# proto4-duplex.net
KiCad netlist of a schematic drawn in EAGLE
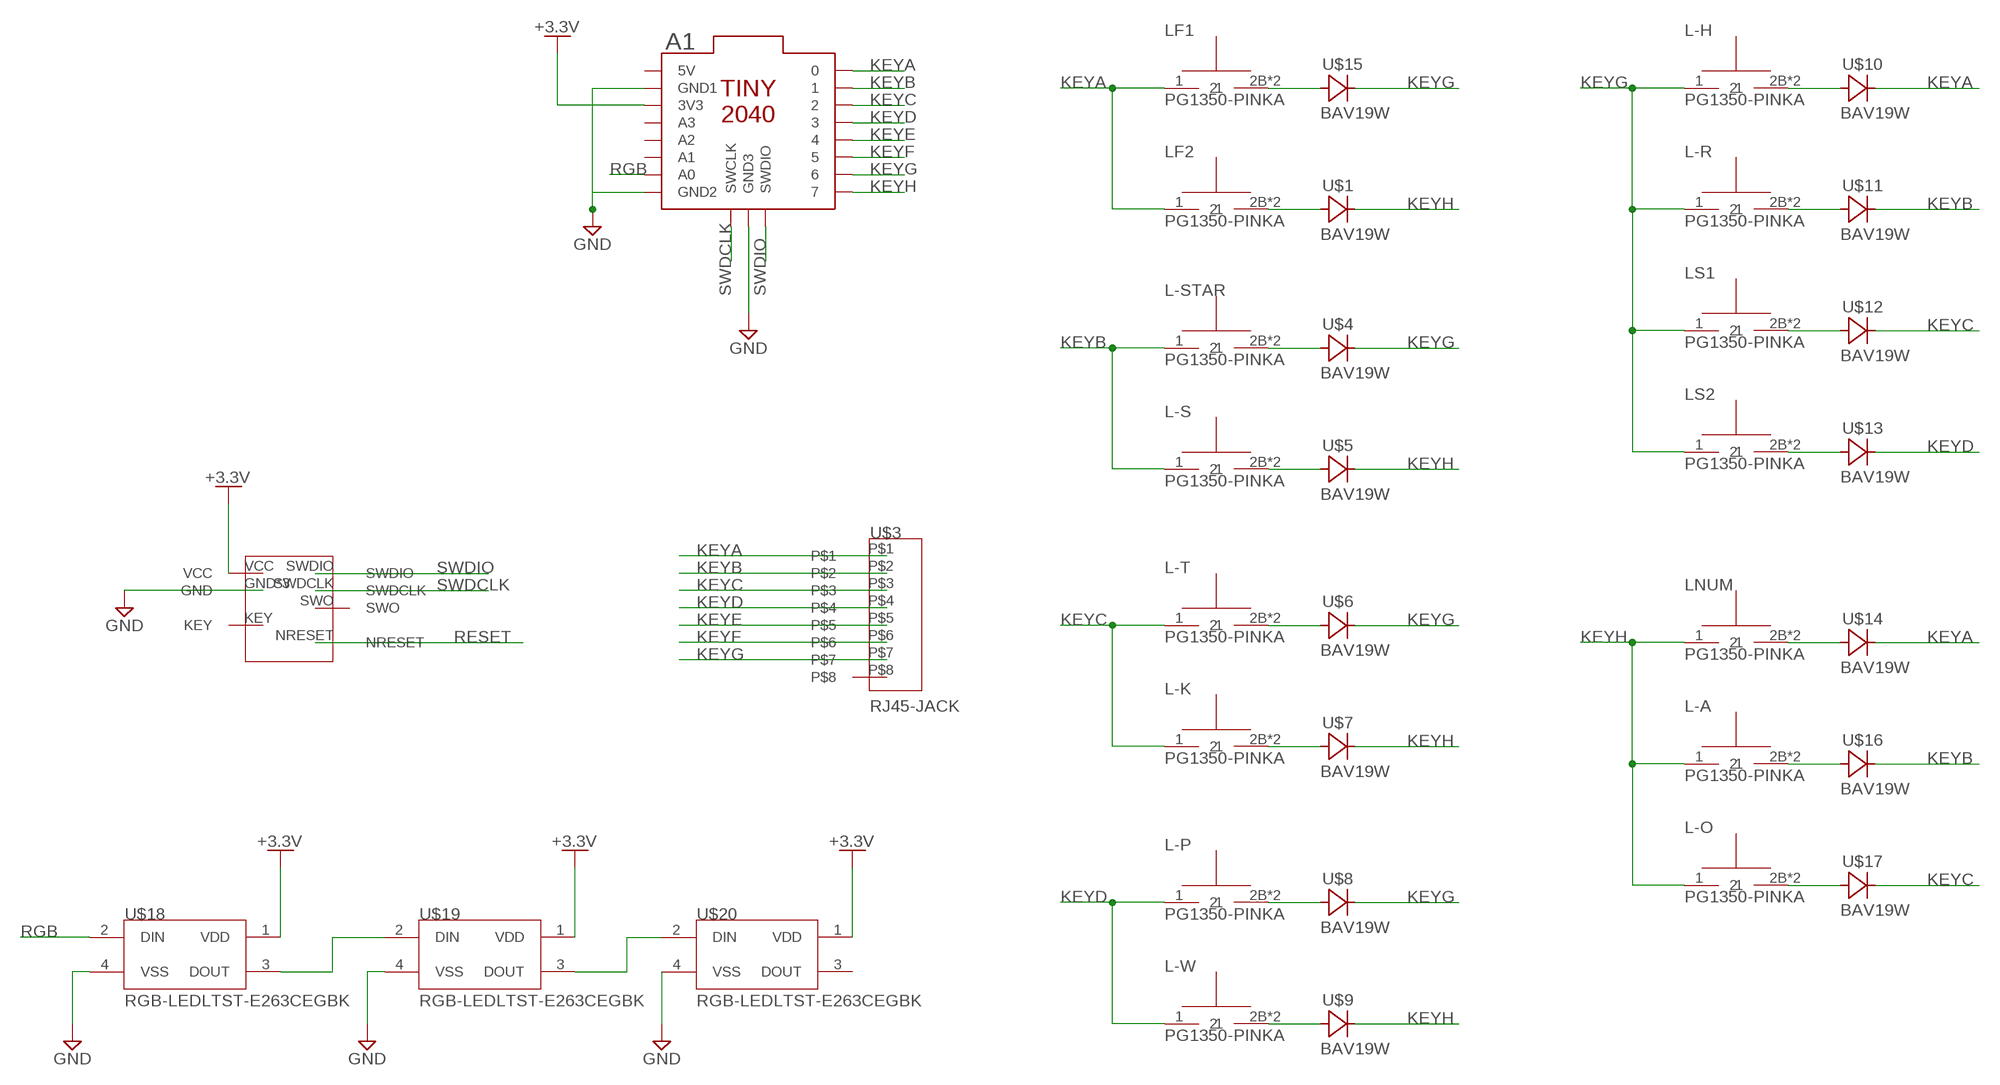
[diagram p0: schematic, sheet 1]

(export (version "E")
  (design (tool "Eeschema 10.0.6"))
  (components
    (comp (ref "A1")
      (value "TINY2040")
      (footprint "eagle-import:TINY2040")
      (libsource (lib "eagle-import") (part "TINY2040"))
    )
    (comp (ref "L-A")
      (value "PG1350-PINKA")
      (footprint "eagle-import:PG1350")
      (libsource (lib "eagle-import") (part "PG1350-PINKA"))
    )
    (comp (ref "L-H")
      (value "PG1350-PINKA")
      (footprint "eagle-import:PG1350")
      (libsource (lib "eagle-import") (part "PG1350-PINKA"))
    )
    (comp (ref "L-K")
      (value "PG1350-PINKA")
      (footprint "eagle-import:PG1350")
      (libsource (lib "eagle-import") (part "PG1350-PINKA"))
    )
    (comp (ref "L-O")
      (value "PG1350-PINKA")
      (footprint "eagle-import:PG1350")
      (libsource (lib "eagle-import") (part "PG1350-PINKA"))
    )
    (comp (ref "L-P")
      (value "PG1350-PINKA")
      (footprint "eagle-import:PG1350")
      (libsource (lib "eagle-import") (part "PG1350-PINKA"))
    )
    (comp (ref "L-R")
      (value "PG1350-PINKA")
      (footprint "eagle-import:PG1350")
      (libsource (lib "eagle-import") (part "PG1350-PINKA"))
    )
    (comp (ref "L-S")
      (value "PG1350-PINKA")
      (footprint "eagle-import:PG1350")
      (libsource (lib "eagle-import") (part "PG1350-PINKA"))
    )
    (comp (ref "L-STAR")
      (value "PG1350-PINKA")
      (footprint "eagle-import:PG1350")
      (libsource (lib "eagle-import") (part "PG1350-PINKA"))
    )
    (comp (ref "L-T")
      (value "PG1350-PINKA")
      (footprint "eagle-import:PG1350")
      (libsource (lib "eagle-import") (part "PG1350-PINKA"))
    )
    (comp (ref "L-W")
      (value "PG1350-PINKA")
      (footprint "eagle-import:PG1350")
      (libsource (lib "eagle-import") (part "PG1350-PINKA"))
    )
    (comp (ref "LF1")
      (value "PG1350-PINKA")
      (footprint "eagle-import:PG1350")
      (libsource (lib "eagle-import") (part "PG1350-PINKA"))
    )
    (comp (ref "LF2")
      (value "PG1350-PINKA")
      (footprint "eagle-import:PG1350")
      (libsource (lib "eagle-import") (part "PG1350-PINKA"))
    )
    (comp (ref "LNUM")
      (value "PG1350-PINKA")
      (footprint "eagle-import:PG1350")
      (libsource (lib "eagle-import") (part "PG1350-PINKA"))
    )
    (comp (ref "LS1")
      (value "PG1350-PINKA")
      (footprint "eagle-import:PG1350")
      (libsource (lib "eagle-import") (part "PG1350-PINKA"))
    )
    (comp (ref "LS2")
      (value "PG1350-PINKA")
      (footprint "eagle-import:PG1350")
      (libsource (lib "eagle-import") (part "PG1350-PINKA"))
    )
    (comp (ref "U$1")
      (value "BAV19W")
      (footprint "eagle-import:SOD123")
      (libsource (lib "eagle-import") (part "BAV19W"))
    )
    (comp (ref "U$2")
      (value "CORTEX-M0")
      (footprint "eagle-import:CORTEX-M10")
      (libsource (lib "eagle-import") (part "CORTEX-M0"))
    )
    (comp (ref "U$3")
      (value "RJ45-JACK")
      (footprint "eagle-import:C-BMJ-0051-RJ45")
      (libsource (lib "eagle-import") (part "RJ45-JACK"))
    )
    (comp (ref "U$4")
      (value "BAV19W")
      (footprint "eagle-import:SOD123")
      (libsource (lib "eagle-import") (part "BAV19W"))
    )
    (comp (ref "U$5")
      (value "BAV19W")
      (footprint "eagle-import:SOD123")
      (libsource (lib "eagle-import") (part "BAV19W"))
    )
    (comp (ref "U$6")
      (value "BAV19W")
      (footprint "eagle-import:SOD123")
      (libsource (lib "eagle-import") (part "BAV19W"))
    )
    (comp (ref "U$7")
      (value "BAV19W")
      (footprint "eagle-import:SOD123")
      (libsource (lib "eagle-import") (part "BAV19W"))
    )
    (comp (ref "U$8")
      (value "BAV19W")
      (footprint "eagle-import:SOD123")
      (libsource (lib "eagle-import") (part "BAV19W"))
    )
    (comp (ref "U$9")
      (value "BAV19W")
      (footprint "eagle-import:SOD123")
      (libsource (lib "eagle-import") (part "BAV19W"))
    )
    (comp (ref "U$10")
      (value "BAV19W")
      (footprint "eagle-import:SOD123")
      (libsource (lib "eagle-import") (part "BAV19W"))
    )
    (comp (ref "U$11")
      (value "BAV19W")
      (footprint "eagle-import:SOD123")
      (libsource (lib "eagle-import") (part "BAV19W"))
    )
    (comp (ref "U$12")
      (value "BAV19W")
      (footprint "eagle-import:SOD123")
      (libsource (lib "eagle-import") (part "BAV19W"))
    )
    (comp (ref "U$13")
      (value "BAV19W")
      (footprint "eagle-import:SOD123")
      (libsource (lib "eagle-import") (part "BAV19W"))
    )
    (comp (ref "U$14")
      (value "BAV19W")
      (footprint "eagle-import:SOD123")
      (libsource (lib "eagle-import") (part "BAV19W"))
    )
    (comp (ref "U$15")
      (value "BAV19W")
      (footprint "eagle-import:SOD123")
      (libsource (lib "eagle-import") (part "BAV19W"))
    )
    (comp (ref "U$16")
      (value "BAV19W")
      (footprint "eagle-import:SOD123")
      (libsource (lib "eagle-import") (part "BAV19W"))
    )
    (comp (ref "U$17")
      (value "BAV19W")
      (footprint "eagle-import:SOD123")
      (libsource (lib "eagle-import") (part "BAV19W"))
    )
    (comp (ref "U$18")
      (value "RGB-LEDLTST-E263CEGBK")
      (footprint "eagle-import:DFN180X180X65-2")
      (libsource (lib "eagle-import") (part "RGB-LEDLTST-E263CEGBK"))
    )
    (comp (ref "U$19")
      (value "RGB-LEDLTST-E263CEGBK")
      (footprint "eagle-import:DFN180X180X65-2")
      (libsource (lib "eagle-import") (part "RGB-LEDLTST-E263CEGBK"))
    )
    (comp (ref "U$20")
      (value "RGB-LEDLTST-E263CEGBK")
      (footprint "eagle-import:DFN180X180X65-2")
      (libsource (lib "eagle-import") (part "RGB-LEDLTST-E263CEGBK"))
    )
  )
  (nets
    (net (code "1") (name "+3.3V") (class "Default")
      (node (ref "A1") (pin "3V3") (pinfunction "3V3_3V3") (pintype "bidirectional"))
      (node (ref "U$18") (pin "1") (pinfunction "VDD_1") (pintype "power_in"))
      (node (ref "U$19") (pin "1") (pinfunction "VDD_1") (pintype "power_in"))
      (node (ref "U$20") (pin "1") (pinfunction "VDD_1") (pintype "power_in"))
    )
    (net (code "2") (name "/KEYA") (class "Default")
      (node (ref "A1") (pin "0") (pinfunction "0_0") (pintype "bidirectional"))
      (node (ref "LF1") (pin "1") (pinfunction "1_1") (pintype "passive"))
      (node (ref "LF2") (pin "1") (pinfunction "1_1") (pintype "passive"))
      (node (ref "U$10") (pin "C") (pinfunction "C_C") (pintype "passive"))
      (node (ref "U$14") (pin "C") (pinfunction "C_C") (pintype "passive"))
      (node (ref "U$3") (pin "P$1") (pinfunction "P$1_P$1") (pintype "bidirectional"))
    )
    (net (code "3") (name "/KEYB") (class "Default")
      (node (ref "A1") (pin "1") (pinfunction "1_1") (pintype "bidirectional"))
      (node (ref "L-S") (pin "1") (pinfunction "1_1") (pintype "passive"))
      (node (ref "L-STAR") (pin "1") (pinfunction "1_1") (pintype "passive"))
      (node (ref "U$11") (pin "C") (pinfunction "C_C") (pintype "passive"))
      (node (ref "U$16") (pin "C") (pinfunction "C_C") (pintype "passive"))
      (node (ref "U$3") (pin "P$2") (pinfunction "P$2_P$2") (pintype "bidirectional"))
    )
    (net (code "4") (name "/KEYC") (class "Default")
      (node (ref "A1") (pin "2") (pinfunction "2_2") (pintype "bidirectional"))
      (node (ref "L-K") (pin "1") (pinfunction "1_1") (pintype "passive"))
      (node (ref "L-T") (pin "1") (pinfunction "1_1") (pintype "passive"))
      (node (ref "U$12") (pin "C") (pinfunction "C_C") (pintype "passive"))
      (node (ref "U$17") (pin "C") (pinfunction "C_C") (pintype "passive"))
      (node (ref "U$3") (pin "P$3") (pinfunction "P$3_P$3") (pintype "bidirectional"))
    )
    (net (code "5") (name "/KEYD") (class "Default")
      (node (ref "A1") (pin "3") (pinfunction "3_3") (pintype "bidirectional"))
      (node (ref "L-P") (pin "1") (pinfunction "1_1") (pintype "passive"))
      (node (ref "L-W") (pin "1") (pinfunction "1_1") (pintype "passive"))
      (node (ref "U$13") (pin "C") (pinfunction "C_C") (pintype "passive"))
      (node (ref "U$3") (pin "P$4") (pinfunction "P$4_P$4") (pintype "bidirectional"))
    )
    (net (code "6") (name "/KEYE") (class "Default")
      (node (ref "A1") (pin "4") (pinfunction "4_4") (pintype "bidirectional"))
      (node (ref "U$3") (pin "P$5") (pinfunction "P$5_P$5") (pintype "bidirectional"))
    )
    (net (code "7") (name "/KEYF") (class "Default")
      (node (ref "A1") (pin "5") (pinfunction "5_5") (pintype "bidirectional"))
      (node (ref "U$3") (pin "P$6") (pinfunction "P$6_P$6") (pintype "bidirectional"))
    )
    (net (code "8") (name "/KEYG") (class "Default")
      (node (ref "A1") (pin "6") (pinfunction "6_6") (pintype "bidirectional"))
      (node (ref "L-H") (pin "1") (pinfunction "1_1") (pintype "passive"))
      (node (ref "L-R") (pin "1") (pinfunction "1_1") (pintype "passive"))
      (node (ref "LS1") (pin "1") (pinfunction "1_1") (pintype "passive"))
      (node (ref "LS2") (pin "1") (pinfunction "1_1") (pintype "passive"))
      (node (ref "U$15") (pin "C") (pinfunction "C_C") (pintype "passive"))
      (node (ref "U$3") (pin "P$7") (pinfunction "P$7_P$7") (pintype "bidirectional"))
      (node (ref "U$4") (pin "C") (pinfunction "C_C") (pintype "passive"))
      (node (ref "U$6") (pin "C") (pinfunction "C_C") (pintype "passive"))
      (node (ref "U$8") (pin "C") (pinfunction "C_C") (pintype "passive"))
    )
    (net (code "9") (name "/KEYH") (class "Default")
      (node (ref "A1") (pin "7") (pinfunction "7_7") (pintype "bidirectional"))
      (node (ref "L-A") (pin "1") (pinfunction "1_1") (pintype "passive"))
      (node (ref "L-O") (pin "1") (pinfunction "1_1") (pintype "passive"))
      (node (ref "LNUM") (pin "1") (pinfunction "1_1") (pintype "passive"))
      (node (ref "U$1") (pin "C") (pinfunction "C_C") (pintype "passive"))
      (node (ref "U$5") (pin "C") (pinfunction "C_C") (pintype "passive"))
      (node (ref "U$7") (pin "C") (pinfunction "C_C") (pintype "passive"))
      (node (ref "U$9") (pin "C") (pinfunction "C_C") (pintype "passive"))
    )
    (net (code "10") (name "/RESET") (class "Default")
      (node (ref "U$2") (pin "NRESET") (pinfunction "NRESET_NRESET") (pintype "bidirectional"))
    )
    (net (code "11") (name "/RGB") (class "Default")
      (node (ref "A1") (pin "A0") (pinfunction "A0_A0") (pintype "bidirectional"))
      (node (ref "U$18") (pin "2") (pinfunction "DIN_2") (pintype "input"))
    )
    (net (code "12") (name "/SWDCLK") (class "Default")
      (node (ref "A1") (pin "SWCLK") (pinfunction "SWCLK_SWCLK") (pintype "bidirectional"))
      (node (ref "U$2") (pin "SWDCLK") (pinfunction "SWDCLK_SWDCLK") (pintype "bidirectional"))
    )
    (net (code "13") (name "/SWDIO") (class "Default")
      (node (ref "A1") (pin "SWDIO") (pinfunction "SWDIO_SWDIO") (pintype "bidirectional"))
      (node (ref "U$2") (pin "SWDIO") (pinfunction "SWDIO_SWDIO") (pintype "bidirectional"))
    )
    (net (code "14") (name "GND") (class "Default")
      (node (ref "A1") (pin "GND1") (pinfunction "GND1_GND1") (pintype "bidirectional"))
      (node (ref "A1") (pin "GND2") (pinfunction "GND2_GND2") (pintype "bidirectional"))
      (node (ref "A1") (pin "GND3") (pinfunction "GND3_GND3") (pintype "bidirectional"))
      (node (ref "U$18") (pin "4") (pinfunction "VSS_4") (pintype "power_in"))
      (node (ref "U$19") (pin "4") (pinfunction "VSS_4") (pintype "power_in"))
      (node (ref "U$2") (pin "GND") (pinfunction "GND_GND") (pintype "bidirectional"))
      (node (ref "U$2") (pin "GND2") (pinfunction "GND_GND2") (pintype "bidirectional"))
      (node (ref "U$2") (pin "GNDDETEC") (pinfunction "GND_GNDDETEC") (pintype "bidirectional"))
      (node (ref "U$20") (pin "4") (pinfunction "VSS_4") (pintype "power_in"))
    )
    (net (code "15") (name "Net-(L-A-2-Pad2B)") (class "Default")
      (node (ref "L-A") (pin "2B") (pinfunction "2_2B") (pintype "passive"))
      (node (ref "L-A") (pin "2T") (pinfunction "2_2T") (pintype "passive"))
      (node (ref "U$16") (pin "A") (pinfunction "A_A") (pintype "passive"))
    )
    (net (code "16") (name "Net-(L-H-2-Pad2B)") (class "Default")
      (node (ref "L-H") (pin "2B") (pinfunction "2_2B") (pintype "passive"))
      (node (ref "L-H") (pin "2T") (pinfunction "2_2T") (pintype "passive"))
      (node (ref "U$10") (pin "A") (pinfunction "A_A") (pintype "passive"))
    )
    (net (code "17") (name "Net-(L-K-2-Pad2B)") (class "Default")
      (node (ref "L-K") (pin "2B") (pinfunction "2_2B") (pintype "passive"))
      (node (ref "L-K") (pin "2T") (pinfunction "2_2T") (pintype "passive"))
      (node (ref "U$7") (pin "A") (pinfunction "A_A") (pintype "passive"))
    )
    (net (code "18") (name "Net-(L-O-2-Pad2B)") (class "Default")
      (node (ref "L-O") (pin "2B") (pinfunction "2_2B") (pintype "passive"))
      (node (ref "L-O") (pin "2T") (pinfunction "2_2T") (pintype "passive"))
      (node (ref "U$17") (pin "A") (pinfunction "A_A") (pintype "passive"))
    )
    (net (code "19") (name "Net-(L-P-2-Pad2B)") (class "Default")
      (node (ref "L-P") (pin "2B") (pinfunction "2_2B") (pintype "passive"))
      (node (ref "L-P") (pin "2T") (pinfunction "2_2T") (pintype "passive"))
      (node (ref "U$8") (pin "A") (pinfunction "A_A") (pintype "passive"))
    )
    (net (code "20") (name "Net-(L-R-2-Pad2B)") (class "Default")
      (node (ref "L-R") (pin "2B") (pinfunction "2_2B") (pintype "passive"))
      (node (ref "L-R") (pin "2T") (pinfunction "2_2T") (pintype "passive"))
      (node (ref "U$11") (pin "A") (pinfunction "A_A") (pintype "passive"))
    )
    (net (code "21") (name "Net-(L-S-2-Pad2B)") (class "Default")
      (node (ref "L-S") (pin "2B") (pinfunction "2_2B") (pintype "passive"))
      (node (ref "L-S") (pin "2T") (pinfunction "2_2T") (pintype "passive"))
      (node (ref "U$5") (pin "A") (pinfunction "A_A") (pintype "passive"))
    )
    (net (code "22") (name "Net-(L-STAR-2-Pad2B)") (class "Default")
      (node (ref "L-STAR") (pin "2B") (pinfunction "2_2B") (pintype "passive"))
      (node (ref "L-STAR") (pin "2T") (pinfunction "2_2T") (pintype "passive"))
      (node (ref "U$4") (pin "A") (pinfunction "A_A") (pintype "passive"))
    )
    (net (code "23") (name "Net-(L-T-2-Pad2B)") (class "Default")
      (node (ref "L-T") (pin "2B") (pinfunction "2_2B") (pintype "passive"))
      (node (ref "L-T") (pin "2T") (pinfunction "2_2T") (pintype "passive"))
      (node (ref "U$6") (pin "A") (pinfunction "A_A") (pintype "passive"))
    )
    (net (code "24") (name "Net-(L-W-2-Pad2B)") (class "Default")
      (node (ref "L-W") (pin "2B") (pinfunction "2_2B") (pintype "passive"))
      (node (ref "L-W") (pin "2T") (pinfunction "2_2T") (pintype "passive"))
      (node (ref "U$9") (pin "A") (pinfunction "A_A") (pintype "passive"))
    )
    (net (code "25") (name "Net-(LF1-2-Pad2B)") (class "Default")
      (node (ref "LF1") (pin "2B") (pinfunction "2_2B") (pintype "passive"))
      (node (ref "LF1") (pin "2T") (pinfunction "2_2T") (pintype "passive"))
      (node (ref "U$15") (pin "A") (pinfunction "A_A") (pintype "passive"))
    )
    (net (code "26") (name "Net-(LF2-2-Pad2B)") (class "Default")
      (node (ref "LF2") (pin "2B") (pinfunction "2_2B") (pintype "passive"))
      (node (ref "LF2") (pin "2T") (pinfunction "2_2T") (pintype "passive"))
      (node (ref "U$1") (pin "A") (pinfunction "A_A") (pintype "passive"))
    )
    (net (code "27") (name "Net-(LNUM-2-Pad2B)") (class "Default")
      (node (ref "LNUM") (pin "2B") (pinfunction "2_2B") (pintype "passive"))
      (node (ref "LNUM") (pin "2T") (pinfunction "2_2T") (pintype "passive"))
      (node (ref "U$14") (pin "A") (pinfunction "A_A") (pintype "passive"))
    )
    (net (code "28") (name "Net-(LS1-2-Pad2B)") (class "Default")
      (node (ref "LS1") (pin "2B") (pinfunction "2_2B") (pintype "passive"))
      (node (ref "LS1") (pin "2T") (pinfunction "2_2T") (pintype "passive"))
      (node (ref "U$12") (pin "A") (pinfunction "A_A") (pintype "passive"))
    )
    (net (code "29") (name "Net-(LS2-2-Pad2B)") (class "Default")
      (node (ref "LS2") (pin "2B") (pinfunction "2_2B") (pintype "passive"))
      (node (ref "LS2") (pin "2T") (pinfunction "2_2T") (pintype "passive"))
      (node (ref "U$13") (pin "A") (pinfunction "A_A") (pintype "passive"))
    )
    (net (code "30") (name "Net-(U$18-DOUT)") (class "Default")
      (node (ref "U$18") (pin "3") (pinfunction "DOUT_3") (pintype "output"))
      (node (ref "U$19") (pin "2") (pinfunction "DIN_2") (pintype "input"))
    )
    (net (code "31") (name "Net-(U$19-DOUT)") (class "Default")
      (node (ref "U$19") (pin "3") (pinfunction "DOUT_3") (pintype "output"))
      (node (ref "U$20") (pin "2") (pinfunction "DIN_2") (pintype "input"))
    )
    (net (code "32") (name "unconnected-(A1-Pad5V)") (class "Default")
      (node (ref "A1") (pin "5V") (pinfunction "5V_5V") (pintype "bidirectional"))
    )
    (net (code "33") (name "unconnected-(A1-PadA1)") (class "Default")
      (node (ref "A1") (pin "A1") (pinfunction "A1_A1") (pintype "bidirectional"))
    )
    (net (code "34") (name "unconnected-(A1-PadA2)") (class "Default")
      (node (ref "A1") (pin "A2") (pinfunction "A2_A2") (pintype "bidirectional"))
    )
    (net (code "35") (name "unconnected-(A1-PadA3)") (class "Default")
      (node (ref "A1") (pin "A3") (pinfunction "A3_A3") (pintype "bidirectional"))
    )
    (net (code "36") (name "unconnected-(U$2-PadKEY)") (class "Default")
      (node (ref "U$2") (pin "KEY") (pinfunction "KEY_KEY") (pintype "bidirectional"))
    )
    (net (code "37") (name "unconnected-(U$2-PadSWO)") (class "Default")
      (node (ref "U$2") (pin "SWO") (pinfunction "SWO_SWO") (pintype "bidirectional"))
    )
    (net (code "38") (name "unconnected-(U$2-PadVCC)") (class "Default")
      (node (ref "U$2") (pin "VCC") (pinfunction "VCC_VCC") (pintype "bidirectional"))
    )
    (net (code "39") (name "unconnected-(U$3-PadP$8)") (class "Default")
      (node (ref "U$3") (pin "P$8") (pinfunction "P$8_P$8") (pintype "bidirectional"))
    )
    (net (code "40") (name "unconnected-(U$20-DOUT-Pad3)") (class "Default")
      (node (ref "U$20") (pin "3") (pinfunction "DOUT_3") (pintype "output"))
    )
  )
)
